# Tiny-G-ZA.net
KiCad netlist of a schematic drawn in EAGLE
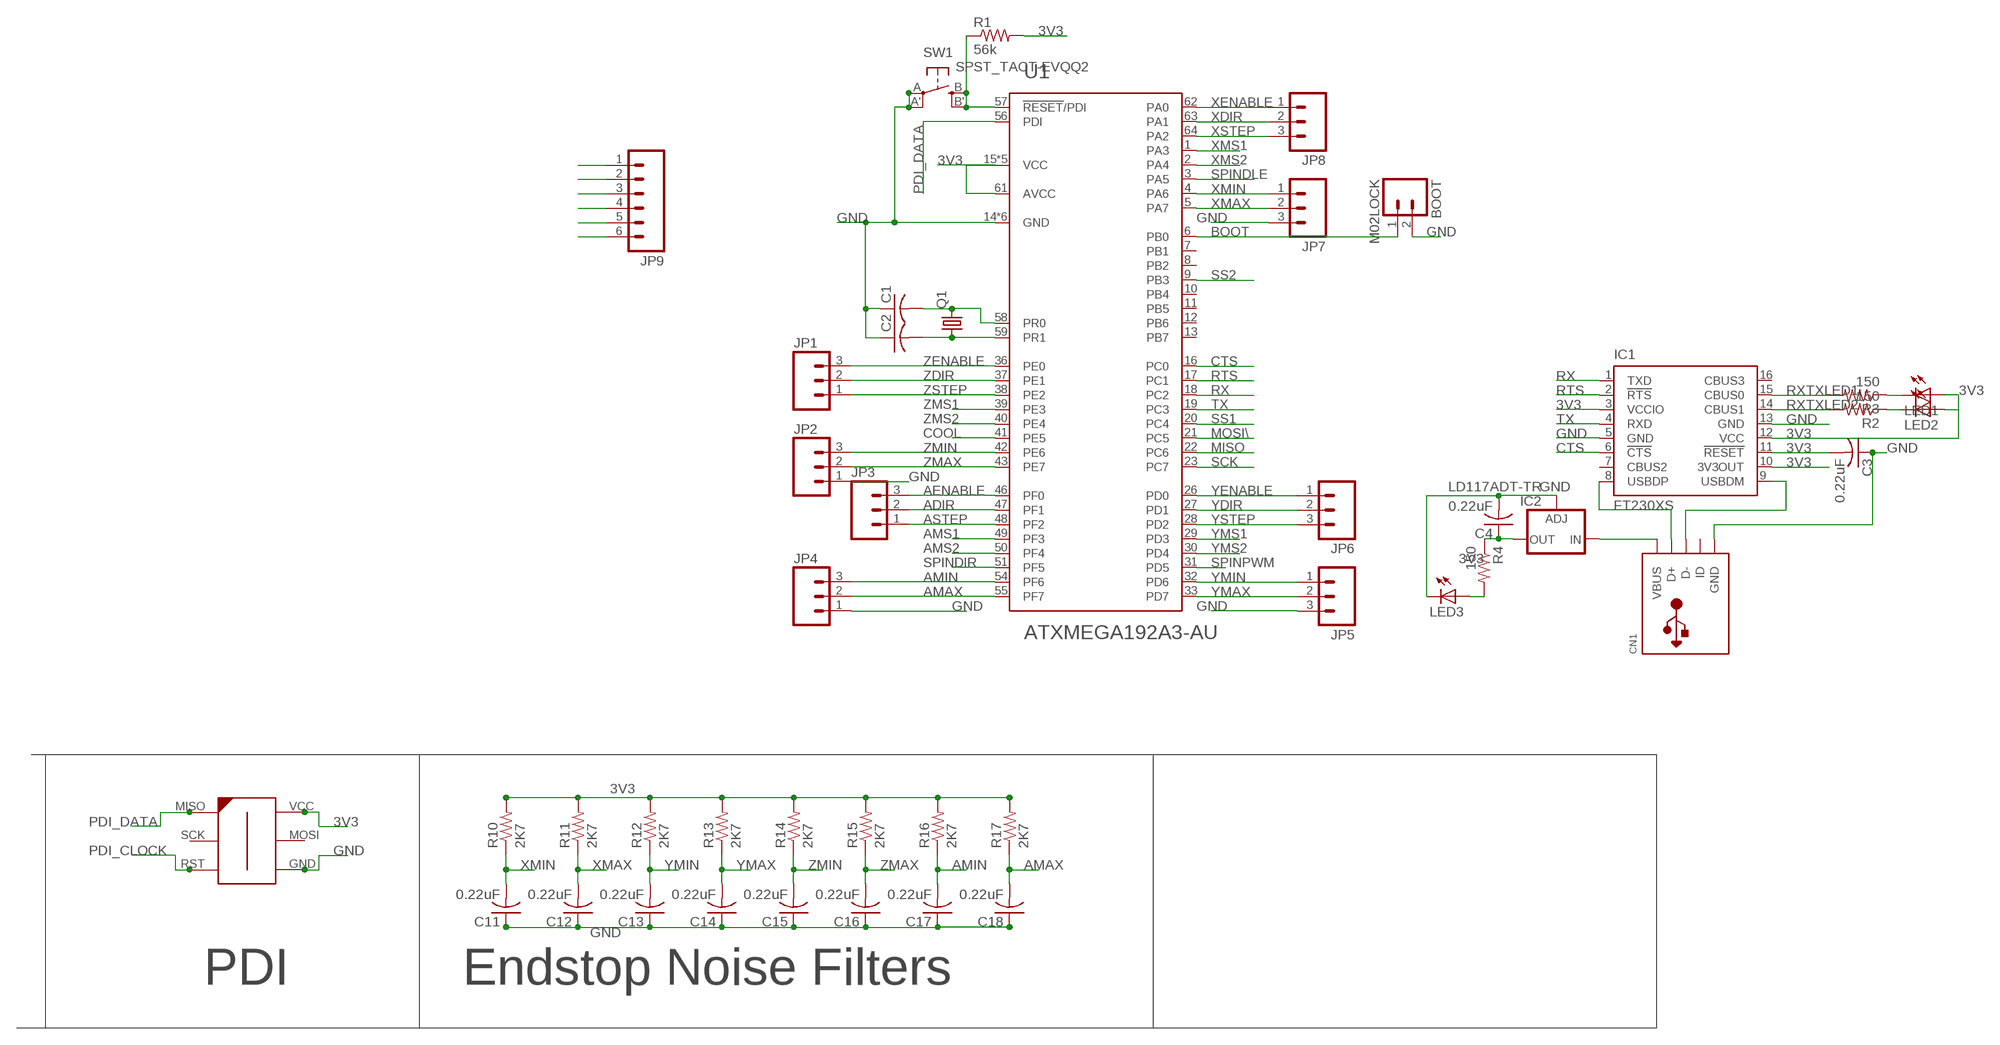
[diagram p0: schematic, sheet 1]

(export (version "E")
  (design (tool "Eeschema 10.0.6"))
  (components
    (comp (ref "BOOT")
      (value "M02LOCK")
      (footprint "eagle-import:1X02_LOCK")
      (libsource (lib "eagle-import") (part "M02LOCK"))
    )
    (comp (ref "C1")
      (value "C-USC1206K")
      (footprint "eagle-import:C1206K")
      (libsource (lib "eagle-import") (part "C-USC1206K"))
    )
    (comp (ref "C2")
      (value "C-USC1206K")
      (footprint "eagle-import:C1206K")
      (libsource (lib "eagle-import") (part "C-USC1206K"))
    )
    (comp (ref "C3")
      (value "0.22uF")
      (footprint "eagle-import:C1206K")
      (libsource (lib "eagle-import") (part "C-USC1206K"))
    )
    (comp (ref "C4")
      (value "0.22uF")
      (footprint "eagle-import:C1206K")
      (libsource (lib "eagle-import") (part "C-USC1206K"))
    )
    (comp (ref "C11")
      (value "0.22uF")
      (footprint "eagle-import:C1206K")
      (libsource (lib "eagle-import") (part "C-USC1206K"))
    )
    (comp (ref "C12")
      (value "0.22uF")
      (footprint "eagle-import:C1206K")
      (libsource (lib "eagle-import") (part "C-USC1206K"))
    )
    (comp (ref "C13")
      (value "0.22uF")
      (footprint "eagle-import:C1206K")
      (libsource (lib "eagle-import") (part "C-USC1206K"))
    )
    (comp (ref "C14")
      (value "0.22uF")
      (footprint "eagle-import:C1206K")
      (libsource (lib "eagle-import") (part "C-USC1206K"))
    )
    (comp (ref "C15")
      (value "0.22uF")
      (footprint "eagle-import:C1206K")
      (libsource (lib "eagle-import") (part "C-USC1206K"))
    )
    (comp (ref "C16")
      (value "0.22uF")
      (footprint "eagle-import:C1206K")
      (libsource (lib "eagle-import") (part "C-USC1206K"))
    )
    (comp (ref "C17")
      (value "0.22uF")
      (footprint "eagle-import:C1206K")
      (libsource (lib "eagle-import") (part "C-USC1206K"))
    )
    (comp (ref "C18")
      (value "0.22uF")
      (footprint "eagle-import:C1206K")
      (libsource (lib "eagle-import") (part "C-USC1206K"))
    )
    (comp (ref "CN1")
      (value "USBMINIB")
      (footprint "eagle-import:USB-MINIB")
      (libsource (lib "eagle-import") (part "USBMINIB"))
    )
    (comp (ref "IC1")
      (value "FT230XS")
      (footprint "eagle-import:SSOP16")
      (libsource (lib "eagle-import") (part "FT230XS"))
    )
    (comp (ref "IC2")
      (value "LD117ADT-TR")
      (footprint "eagle-import:DPACK")
      (libsource (lib "eagle-import") (part "LD117A?DT-TR"))
    )
    (comp (ref "JP1")
      (value "M03LONGPADS")
      (footprint "eagle-import:1X03_LONGPADS")
      (libsource (lib "eagle-import") (part "M03LONGPADS"))
    )
    (comp (ref "JP2")
      (value "M03LONGPADS")
      (footprint "eagle-import:1X03_LONGPADS")
      (libsource (lib "eagle-import") (part "M03LONGPADS"))
    )
    (comp (ref "JP3")
      (value "M03LONGPADS")
      (footprint "eagle-import:1X03_LONGPADS")
      (libsource (lib "eagle-import") (part "M03LONGPADS"))
    )
    (comp (ref "JP4")
      (value "M03LONGPADS")
      (footprint "eagle-import:1X03_LONGPADS")
      (libsource (lib "eagle-import") (part "M03LONGPADS"))
    )
    (comp (ref "JP5")
      (value "M03LONGPADS")
      (footprint "eagle-import:1X03_LONGPADS")
      (libsource (lib "eagle-import") (part "M03LONGPADS"))
    )
    (comp (ref "JP6")
      (value "M03LONGPADS")
      (footprint "eagle-import:1X03_LONGPADS")
      (libsource (lib "eagle-import") (part "M03LONGPADS"))
    )
    (comp (ref "JP7")
      (value "M03LONGPADS")
      (footprint "eagle-import:1X03_LONGPADS")
      (libsource (lib "eagle-import") (part "M03LONGPADS"))
    )
    (comp (ref "JP8")
      (value "M03LONGPADS")
      (footprint "eagle-import:1X03_LONGPADS")
      (libsource (lib "eagle-import") (part "M03LONGPADS"))
    )
    (comp (ref "JP9")
      (value "M06LONGPADS")
      (footprint "eagle-import:1X06_LONGPADS")
      (libsource (lib "eagle-import") (part "M06LONGPADS"))
    )
    (comp (ref "LED1")
      (value "LEDSMT1206")
      (footprint "eagle-import:1206")
      (libsource (lib "eagle-import") (part "LEDSMT1206"))
    )
    (comp (ref "LED2")
      (value "LEDSMT1206")
      (footprint "eagle-import:1206")
      (libsource (lib "eagle-import") (part "LEDSMT1206"))
    )
    (comp (ref "LED3")
      (value "LEDSMT1206")
      (footprint "eagle-import:1206")
      (libsource (lib "eagle-import") (part "LEDSMT1206"))
    )
    (comp (ref "Q1")
      (value "CRYSTALHC49UP")
      (footprint "eagle-import:HC49UP")
      (libsource (lib "eagle-import") (part "CRYSTALHC49UP"))
    )
    (comp (ref "R1")
      (value "56k")
      (footprint "eagle-import:M1206")
      (libsource (lib "eagle-import") (part "R-US_M1206"))
    )
    (comp (ref "R2")
      (value "150")
      (footprint "eagle-import:M1206")
      (libsource (lib "eagle-import") (part "R-US_M1206"))
    )
    (comp (ref "R3")
      (value "150")
      (footprint "eagle-import:M1206")
      (libsource (lib "eagle-import") (part "R-US_M1206"))
    )
    (comp (ref "R4")
      (value "150")
      (footprint "eagle-import:M1206")
      (libsource (lib "eagle-import") (part "R-US_M1206"))
    )
    (comp (ref "R10")
      (value "2K7")
      (footprint "eagle-import:M1206")
      (libsource (lib "eagle-import") (part "R-US_M1206"))
    )
    (comp (ref "R11")
      (value "2K7")
      (footprint "eagle-import:M1206")
      (libsource (lib "eagle-import") (part "R-US_M1206"))
    )
    (comp (ref "R12")
      (value "2K7")
      (footprint "eagle-import:M1206")
      (libsource (lib "eagle-import") (part "R-US_M1206"))
    )
    (comp (ref "R13")
      (value "2K7")
      (footprint "eagle-import:M1206")
      (libsource (lib "eagle-import") (part "R-US_M1206"))
    )
    (comp (ref "R14")
      (value "2K7")
      (footprint "eagle-import:M1206")
      (libsource (lib "eagle-import") (part "R-US_M1206"))
    )
    (comp (ref "R15")
      (value "2K7")
      (footprint "eagle-import:M1206")
      (libsource (lib "eagle-import") (part "R-US_M1206"))
    )
    (comp (ref "R16")
      (value "2K7")
      (footprint "eagle-import:M1206")
      (libsource (lib "eagle-import") (part "R-US_M1206"))
    )
    (comp (ref "R17")
      (value "2K7")
      (footprint "eagle-import:M1206")
      (libsource (lib "eagle-import") (part "R-US_M1206"))
    )
    (comp (ref "SW1")
      (value "SPST_TACT-EVQQ2")
      (footprint "eagle-import:EVQ-Q2")
      (libsource (lib "eagle-import") (part "SPST_TACT-EVQQ2"))
    )
    (comp (ref "U$1")
      (value "AVR-ISP-6-EDGE")
      (footprint "eagle-import:6PAD_ISP")
      (libsource (lib "eagle-import") (part "AVR-ISP-6-EDGE"))
    )
    (comp (ref "U1")
      (value "ATXMEGA192A3-AU")
      (footprint "eagle-import:TQFP-64A-64")
      (libsource (lib "eagle-import") (part "ATXMEGA192A3-AU"))
    )
  )
  (nets
    (net (code "1") (name "/3V3") (class "Default")
      (node (ref "C3") (pin "2") (pinfunction "2_2") (pintype "passive"))
      (node (ref "C4") (pin "1") (pinfunction "1_1") (pintype "passive"))
      (node (ref "IC1") (pin "10") (pinfunction "3V3OUT_10") (pintype "output"))
      (node (ref "IC1") (pin "11") (pinfunction "~{RESET}_11") (pintype "input"))
      (node (ref "IC1") (pin "12") (pinfunction "VCC_12") (pintype "power_in"))
      (node (ref "IC1") (pin "3") (pinfunction "VCCIO_3") (pintype "power_in"))
      (node (ref "IC2") (pin "4") (pinfunction "OUT_4") (pintype "passive"))
      (node (ref "JP9") (pin "1") (pinfunction "1_1") (pintype "passive"))
      (node (ref "LED1") (pin "A") (pinfunction "A_A") (pintype "passive"))
      (node (ref "LED2") (pin "A") (pinfunction "A_A") (pintype "passive"))
      (node (ref "R1") (pin "2") (pinfunction "2_2") (pintype "passive"))
      (node (ref "R10") (pin "2") (pinfunction "2_2") (pintype "passive"))
      (node (ref "R11") (pin "2") (pinfunction "2_2") (pintype "passive"))
      (node (ref "R12") (pin "2") (pinfunction "2_2") (pintype "passive"))
      (node (ref "R13") (pin "2") (pinfunction "2_2") (pintype "passive"))
      (node (ref "R14") (pin "2") (pinfunction "2_2") (pintype "passive"))
      (node (ref "R15") (pin "2") (pinfunction "2_2") (pintype "passive"))
      (node (ref "R16") (pin "2") (pinfunction "2_2") (pintype "passive"))
      (node (ref "R17") (pin "2") (pinfunction "2_2") (pintype "passive"))
      (node (ref "R4") (pin "1") (pinfunction "1_1") (pintype "passive"))
      (node (ref "U$1") (pin "VCC") (pinfunction "P$6_VCC") (pintype "bidirectional"))
      (node (ref "U1") (pin "15") (pinfunction "VCC_15") (pintype "power_in"))
      (node (ref "U1") (pin "25") (pinfunction "VCC_25") (pintype "power_in"))
      (node (ref "U1") (pin "35") (pinfunction "VCC_35") (pintype "power_in"))
      (node (ref "U1") (pin "45") (pinfunction "VCC_45") (pintype "power_in"))
      (node (ref "U1") (pin "53") (pinfunction "VCC_53") (pintype "power_in"))
      (node (ref "U1") (pin "61") (pinfunction "AVCC_61") (pintype "power_in"))
    )
    (net (code "2") (name "/ADIR") (class "Default")
      (node (ref "JP3") (pin "2") (pinfunction "2_2") (pintype "passive"))
      (node (ref "U1") (pin "47") (pinfunction "PF1_47") (pintype "bidirectional"))
    )
    (net (code "3") (name "/AENABLE") (class "Default")
      (node (ref "JP3") (pin "3") (pinfunction "3_3") (pintype "passive"))
      (node (ref "U1") (pin "46") (pinfunction "PF0_46") (pintype "bidirectional"))
    )
    (net (code "4") (name "/AMAX") (class "Default")
      (node (ref "C18") (pin "2") (pinfunction "2_2") (pintype "passive"))
      (node (ref "JP4") (pin "2") (pinfunction "2_2") (pintype "passive"))
      (node (ref "R17") (pin "1") (pinfunction "1_1") (pintype "passive"))
      (node (ref "U1") (pin "55") (pinfunction "PF7_55") (pintype "bidirectional"))
    )
    (net (code "5") (name "/AMIN") (class "Default")
      (node (ref "C17") (pin "2") (pinfunction "2_2") (pintype "passive"))
      (node (ref "JP4") (pin "3") (pinfunction "3_3") (pintype "passive"))
      (node (ref "R16") (pin "1") (pinfunction "1_1") (pintype "passive"))
      (node (ref "U1") (pin "54") (pinfunction "PF6_54") (pintype "bidirectional"))
    )
    (net (code "6") (name "/AMS1") (class "Default")
      (node (ref "U1") (pin "49") (pinfunction "PF3_49") (pintype "bidirectional"))
    )
    (net (code "7") (name "/AMS2") (class "Default")
      (node (ref "U1") (pin "50") (pinfunction "PF4_50") (pintype "bidirectional"))
    )
    (net (code "8") (name "/ASTEP") (class "Default")
      (node (ref "JP3") (pin "1") (pinfunction "1_1") (pintype "passive"))
      (node (ref "U1") (pin "48") (pinfunction "PF2_48") (pintype "bidirectional"))
    )
    (net (code "9") (name "/BOOT") (class "Default")
      (node (ref "BOOT") (pin "1") (pinfunction "1_1") (pintype "passive"))
      (node (ref "U1") (pin "6") (pinfunction "PB0_6") (pintype "bidirectional"))
    )
    (net (code "10") (name "/COOL") (class "Default")
      (node (ref "JP9") (pin "6") (pinfunction "6_6") (pintype "passive"))
      (node (ref "U1") (pin "41") (pinfunction "PE5_41") (pintype "bidirectional"))
    )
    (net (code "11") (name "/CTS") (class "Default")
      (node (ref "IC1") (pin "6") (pinfunction "~{CTS}_6") (pintype "input"))
      (node (ref "U1") (pin "16") (pinfunction "PC0_16") (pintype "bidirectional"))
    )
    (net (code "12") (name "/GND") (class "Default")
      (node (ref "BOOT") (pin "2") (pinfunction "2_2") (pintype "passive"))
      (node (ref "C1") (pin "1") (pinfunction "1_1") (pintype "passive"))
      (node (ref "C11") (pin "1") (pinfunction "1_1") (pintype "passive"))
      (node (ref "C12") (pin "1") (pinfunction "1_1") (pintype "passive"))
      (node (ref "C13") (pin "1") (pinfunction "1_1") (pintype "passive"))
      (node (ref "C14") (pin "1") (pinfunction "1_1") (pintype "passive"))
      (node (ref "C15") (pin "1") (pinfunction "1_1") (pintype "passive"))
      (node (ref "C16") (pin "1") (pinfunction "1_1") (pintype "passive"))
      (node (ref "C17") (pin "1") (pinfunction "1_1") (pintype "passive"))
      (node (ref "C18") (pin "1") (pinfunction "1_1") (pintype "passive"))
      (node (ref "C2") (pin "1") (pinfunction "1_1") (pintype "passive"))
      (node (ref "C3") (pin "1") (pinfunction "1_1") (pintype "passive"))
      (node (ref "C4") (pin "2") (pinfunction "2_2") (pintype "passive"))
      (node (ref "CN1") (pin "GND") (pinfunction "GND_GND") (pintype "power_in"))
      (node (ref "IC1") (pin "13") (pinfunction "GND_13") (pintype "power_in"))
      (node (ref "IC1") (pin "5") (pinfunction "GND_5") (pintype "power_in"))
      (node (ref "IC2") (pin "1") (pinfunction "ADJ_1") (pintype "input"))
      (node (ref "JP2") (pin "1") (pinfunction "1_1") (pintype "passive"))
      (node (ref "JP4") (pin "1") (pinfunction "1_1") (pintype "passive"))
      (node (ref "JP5") (pin "3") (pinfunction "3_3") (pintype "passive"))
      (node (ref "JP7") (pin "3") (pinfunction "3_3") (pintype "passive"))
      (node (ref "JP9") (pin "2") (pinfunction "2_2") (pintype "passive"))
      (node (ref "LED3") (pin "C") (pinfunction "C_C") (pintype "passive"))
      (node (ref "SW1") (pin "A") (pinfunction "P_A") (pintype "passive"))
      (node (ref "SW1") (pin "A'") (pinfunction "P1_A'") (pintype "passive"))
      (node (ref "U$1") (pin "GND") (pinfunction "P$4_GND") (pintype "bidirectional"))
      (node (ref "U1") (pin "14") (pinfunction "GND_14") (pintype "power_in"))
      (node (ref "U1") (pin "24") (pinfunction "GND_24") (pintype "power_in"))
      (node (ref "U1") (pin "34") (pinfunction "GND_34") (pintype "power_in"))
      (node (ref "U1") (pin "44") (pinfunction "GND_44") (pintype "power_in"))
      (node (ref "U1") (pin "52") (pinfunction "GND_52") (pintype "power_in"))
      (node (ref "U1") (pin "60") (pinfunction "GND_60") (pintype "power_in"))
    )
    (net (code "13") (name "/MISO") (class "Default")
      (node (ref "U1") (pin "22") (pinfunction "PC6_22") (pintype "bidirectional"))
    )
    (net (code "14") (name "/MOSI\\") (class "Default")
      (node (ref "U1") (pin "21") (pinfunction "PC5_21") (pintype "bidirectional"))
    )
    (net (code "15") (name "/PDI_CLOCK") (class "Default")
      (node (ref "R1") (pin "1") (pinfunction "1_1") (pintype "passive"))
      (node (ref "SW1") (pin "B") (pinfunction "S_B") (pintype "passive"))
      (node (ref "SW1") (pin "B'") (pinfunction "S1_B'") (pintype "passive"))
      (node (ref "U$1") (pin "RST") (pinfunction "P$3_RST") (pintype "bidirectional"))
      (node (ref "U1") (pin "57") (pinfunction "~{RESET}/PDI_57") (pintype "bidirectional"))
    )
    (net (code "16") (name "/PDI_DATA") (class "Default")
      (node (ref "U$1") (pin "MISO") (pinfunction "P$1_MISO") (pintype "bidirectional"))
      (node (ref "U1") (pin "56") (pinfunction "PDI_56") (pintype "bidirectional"))
    )
    (net (code "17") (name "/RTS") (class "Default")
      (node (ref "IC1") (pin "2") (pinfunction "~{RTS}_2") (pintype "output"))
      (node (ref "U1") (pin "17") (pinfunction "PC1_17") (pintype "bidirectional"))
    )
    (net (code "18") (name "/RX") (class "Default")
      (node (ref "IC1") (pin "1") (pinfunction "TXD_1") (pintype "output"))
      (node (ref "U1") (pin "18") (pinfunction "PC2_18") (pintype "bidirectional"))
    )
    (net (code "19") (name "/RXTXLED1") (class "Default")
      (node (ref "IC1") (pin "15") (pinfunction "CBUS0_15") (pintype "bidirectional"))
      (node (ref "R3") (pin "2") (pinfunction "2_2") (pintype "passive"))
    )
    (net (code "20") (name "/RXTXLED2") (class "Default")
      (node (ref "IC1") (pin "14") (pinfunction "CBUS1_14") (pintype "bidirectional"))
      (node (ref "R2") (pin "2") (pinfunction "2_2") (pintype "passive"))
    )
    (net (code "21") (name "/SCK") (class "Default")
      (node (ref "U1") (pin "23") (pinfunction "PC7_23") (pintype "bidirectional"))
    )
    (net (code "22") (name "/SPINDIR") (class "Default")
      (node (ref "JP9") (pin "5") (pinfunction "5_5") (pintype "passive"))
      (node (ref "U1") (pin "51") (pinfunction "PF5_51") (pintype "bidirectional"))
    )
    (net (code "23") (name "/SPINDLE") (class "Default")
      (node (ref "JP9") (pin "3") (pinfunction "3_3") (pintype "passive"))
      (node (ref "U1") (pin "3") (pinfunction "PA5_3") (pintype "bidirectional"))
    )
    (net (code "24") (name "/SPINPWM") (class "Default")
      (node (ref "JP9") (pin "4") (pinfunction "4_4") (pintype "passive"))
      (node (ref "U1") (pin "31") (pinfunction "PD5_31") (pintype "bidirectional"))
    )
    (net (code "25") (name "/SS1") (class "Default")
      (node (ref "U1") (pin "20") (pinfunction "PC4_20") (pintype "bidirectional"))
    )
    (net (code "26") (name "/SS2") (class "Default")
      (node (ref "U1") (pin "9") (pinfunction "PB3_9") (pintype "bidirectional"))
    )
    (net (code "27") (name "/TX") (class "Default")
      (node (ref "IC1") (pin "4") (pinfunction "RXD_4") (pintype "input"))
      (node (ref "U1") (pin "19") (pinfunction "PC3_19") (pintype "bidirectional"))
    )
    (net (code "28") (name "/XDIR") (class "Default")
      (node (ref "JP8") (pin "2") (pinfunction "2_2") (pintype "passive"))
      (node (ref "U1") (pin "63") (pinfunction "PA1_63") (pintype "bidirectional"))
    )
    (net (code "29") (name "/XENABLE") (class "Default")
      (node (ref "JP8") (pin "1") (pinfunction "1_1") (pintype "passive"))
      (node (ref "U1") (pin "62") (pinfunction "PA0_62") (pintype "bidirectional"))
    )
    (net (code "30") (name "/XMAX") (class "Default")
      (node (ref "C12") (pin "2") (pinfunction "2_2") (pintype "passive"))
      (node (ref "JP7") (pin "2") (pinfunction "2_2") (pintype "passive"))
      (node (ref "R11") (pin "1") (pinfunction "1_1") (pintype "passive"))
      (node (ref "U1") (pin "5") (pinfunction "PA7_5") (pintype "bidirectional"))
    )
    (net (code "31") (name "/XMIN") (class "Default")
      (node (ref "C11") (pin "2") (pinfunction "2_2") (pintype "passive"))
      (node (ref "JP7") (pin "1") (pinfunction "1_1") (pintype "passive"))
      (node (ref "R10") (pin "1") (pinfunction "1_1") (pintype "passive"))
      (node (ref "U1") (pin "4") (pinfunction "PA6_4") (pintype "bidirectional"))
    )
    (net (code "32") (name "/XMS1") (class "Default")
      (node (ref "U1") (pin "1") (pinfunction "PA3_1") (pintype "bidirectional"))
    )
    (net (code "33") (name "/XMS2") (class "Default")
      (node (ref "U1") (pin "2") (pinfunction "PA4_2") (pintype "bidirectional"))
    )
    (net (code "34") (name "/XSTEP") (class "Default")
      (node (ref "JP8") (pin "3") (pinfunction "3_3") (pintype "passive"))
      (node (ref "U1") (pin "64") (pinfunction "PA2_64") (pintype "bidirectional"))
    )
    (net (code "35") (name "/YDIR") (class "Default")
      (node (ref "JP6") (pin "2") (pinfunction "2_2") (pintype "passive"))
      (node (ref "U1") (pin "27") (pinfunction "PD1_27") (pintype "bidirectional"))
    )
    (net (code "36") (name "/YENABLE") (class "Default")
      (node (ref "JP6") (pin "1") (pinfunction "1_1") (pintype "passive"))
      (node (ref "U1") (pin "26") (pinfunction "PD0_26") (pintype "bidirectional"))
    )
    (net (code "37") (name "/YMAX") (class "Default")
      (node (ref "C14") (pin "2") (pinfunction "2_2") (pintype "passive"))
      (node (ref "JP5") (pin "2") (pinfunction "2_2") (pintype "passive"))
      (node (ref "R13") (pin "1") (pinfunction "1_1") (pintype "passive"))
      (node (ref "U1") (pin "33") (pinfunction "PD7_33") (pintype "bidirectional"))
    )
    (net (code "38") (name "/YMIN") (class "Default")
      (node (ref "C13") (pin "2") (pinfunction "2_2") (pintype "passive"))
      (node (ref "JP5") (pin "1") (pinfunction "1_1") (pintype "passive"))
      (node (ref "R12") (pin "1") (pinfunction "1_1") (pintype "passive"))
      (node (ref "U1") (pin "32") (pinfunction "PD6_32") (pintype "bidirectional"))
    )
    (net (code "39") (name "/YMS1") (class "Default")
      (node (ref "U1") (pin "29") (pinfunction "PD3_29") (pintype "bidirectional"))
    )
    (net (code "40") (name "/YMS2") (class "Default")
      (node (ref "U1") (pin "30") (pinfunction "PD4_30") (pintype "bidirectional"))
    )
    (net (code "41") (name "/YSTEP") (class "Default")
      (node (ref "JP6") (pin "3") (pinfunction "3_3") (pintype "passive"))
      (node (ref "U1") (pin "28") (pinfunction "PD2_28") (pintype "bidirectional"))
    )
    (net (code "42") (name "/ZDIR") (class "Default")
      (node (ref "JP1") (pin "2") (pinfunction "2_2") (pintype "passive"))
      (node (ref "U1") (pin "37") (pinfunction "PE1_37") (pintype "bidirectional"))
    )
    (net (code "43") (name "/ZENABLE") (class "Default")
      (node (ref "JP1") (pin "3") (pinfunction "3_3") (pintype "passive"))
      (node (ref "U1") (pin "36") (pinfunction "PE0_36") (pintype "bidirectional"))
    )
    (net (code "44") (name "/ZMAX") (class "Default")
      (node (ref "C16") (pin "2") (pinfunction "2_2") (pintype "passive"))
      (node (ref "JP2") (pin "2") (pinfunction "2_2") (pintype "passive"))
      (node (ref "R15") (pin "1") (pinfunction "1_1") (pintype "passive"))
      (node (ref "U1") (pin "43") (pinfunction "PE7_43") (pintype "bidirectional"))
    )
    (net (code "45") (name "/ZMIN") (class "Default")
      (node (ref "C15") (pin "2") (pinfunction "2_2") (pintype "passive"))
      (node (ref "JP2") (pin "3") (pinfunction "3_3") (pintype "passive"))
      (node (ref "R14") (pin "1") (pinfunction "1_1") (pintype "passive"))
      (node (ref "U1") (pin "42") (pinfunction "PE6_42") (pintype "bidirectional"))
    )
    (net (code "46") (name "/ZMS1") (class "Default")
      (node (ref "U1") (pin "39") (pinfunction "PE3_39") (pintype "bidirectional"))
    )
    (net (code "47") (name "/ZMS2") (class "Default")
      (node (ref "U1") (pin "40") (pinfunction "PE4_40") (pintype "bidirectional"))
    )
    (net (code "48") (name "/ZSTEP") (class "Default")
      (node (ref "JP1") (pin "1") (pinfunction "1_1") (pintype "passive"))
      (node (ref "U1") (pin "38") (pinfunction "PE2_38") (pintype "bidirectional"))
    )
    (net (code "49") (name "Net-(IC1-USBDM)") (class "Default")
      (node (ref "CN1") (pin "D-") (pinfunction "D-_D-") (pintype "bidirectional"))
      (node (ref "IC1") (pin "9") (pinfunction "USBDM_9") (pintype "input"))
    )
    (net (code "50") (name "Net-(IC1-USBDP)") (class "Default")
      (node (ref "CN1") (pin "D+") (pinfunction "D+_D+") (pintype "bidirectional"))
      (node (ref "IC1") (pin "8") (pinfunction "USBDP_8") (pintype "input"))
    )
    (net (code "51") (name "Net-(IC2-IN)") (class "Default")
      (node (ref "CN1") (pin "VBUS") (pinfunction "VBUS_VBUS") (pintype "power_in"))
      (node (ref "IC2") (pin "3") (pinfunction "IN_3") (pintype "input"))
    )
    (net (code "52") (name "Net-(LED1-PadC)") (class "Default")
      (node (ref "LED1") (pin "C") (pinfunction "C_C") (pintype "passive"))
      (node (ref "R3") (pin "1") (pinfunction "1_1") (pintype "passive"))
    )
    (net (code "53") (name "Net-(LED2-PadC)") (class "Default")
      (node (ref "LED2") (pin "C") (pinfunction "C_C") (pintype "passive"))
      (node (ref "R2") (pin "1") (pinfunction "1_1") (pintype "passive"))
    )
    (net (code "54") (name "Net-(LED3-PadA)") (class "Default")
      (node (ref "LED3") (pin "A") (pinfunction "A_A") (pintype "passive"))
      (node (ref "R4") (pin "2") (pinfunction "2_2") (pintype "passive"))
    )
    (net (code "55") (name "Net-(U1-PR0)") (class "Default")
      (node (ref "C1") (pin "2") (pinfunction "2_2") (pintype "passive"))
      (node (ref "Q1") (pin "2") (pinfunction "2_2") (pintype "passive"))
      (node (ref "U1") (pin "58") (pinfunction "PR0_58") (pintype "bidirectional"))
    )
    (net (code "56") (name "Net-(U1-PR1)") (class "Default")
      (node (ref "C2") (pin "2") (pinfunction "2_2") (pintype "passive"))
      (node (ref "Q1") (pin "1") (pinfunction "1_1") (pintype "passive"))
      (node (ref "U1") (pin "59") (pinfunction "PR1_59") (pintype "bidirectional"))
    )
    (net (code "57") (name "unconnected-(CN1-PadID)") (class "Default")
      (node (ref "CN1") (pin "ID") (pinfunction "ID_ID") (pintype "bidirectional"))
    )
    (net (code "58") (name "unconnected-(IC1-CBUS2-Pad7)") (class "Default")
      (node (ref "IC1") (pin "7") (pinfunction "CBUS2_7") (pintype "bidirectional"))
    )
    (net (code "59") (name "unconnected-(IC1-CBUS3-Pad16)") (class "Default")
      (node (ref "IC1") (pin "16") (pinfunction "CBUS3_16") (pintype "bidirectional"))
    )
    (net (code "60") (name "unconnected-(U$1-P$2-PadSCK)") (class "Default")
      (node (ref "U$1") (pin "SCK") (pinfunction "P$2_SCK") (pintype "bidirectional"))
    )
    (net (code "61") (name "unconnected-(U$1-P$5-PadMOSI)") (class "Default")
      (node (ref "U$1") (pin "MOSI") (pinfunction "P$5_MOSI") (pintype "bidirectional"))
    )
    (net (code "62") (name "unconnected-(U1-PB1-Pad7)") (class "Default")
      (node (ref "U1") (pin "7") (pinfunction "PB1_7") (pintype "bidirectional"))
    )
    (net (code "63") (name "unconnected-(U1-PB2-Pad8)") (class "Default")
      (node (ref "U1") (pin "8") (pinfunction "PB2_8") (pintype "bidirectional"))
    )
    (net (code "64") (name "unconnected-(U1-PB4-Pad10)") (class "Default")
      (node (ref "U1") (pin "10") (pinfunction "PB4_10") (pintype "bidirectional"))
    )
    (net (code "65") (name "unconnected-(U1-PB5-Pad11)") (class "Default")
      (node (ref "U1") (pin "11") (pinfunction "PB5_11") (pintype "bidirectional"))
    )
    (net (code "66") (name "unconnected-(U1-PB6-Pad12)") (class "Default")
      (node (ref "U1") (pin "12") (pinfunction "PB6_12") (pintype "bidirectional"))
    )
    (net (code "67") (name "unconnected-(U1-PB7-Pad13)") (class "Default")
      (node (ref "U1") (pin "13") (pinfunction "PB7_13") (pintype "bidirectional"))
    )
  )
)
